# PCLaser.net
KiCad netlist of a schematic drawn in Altium Designer
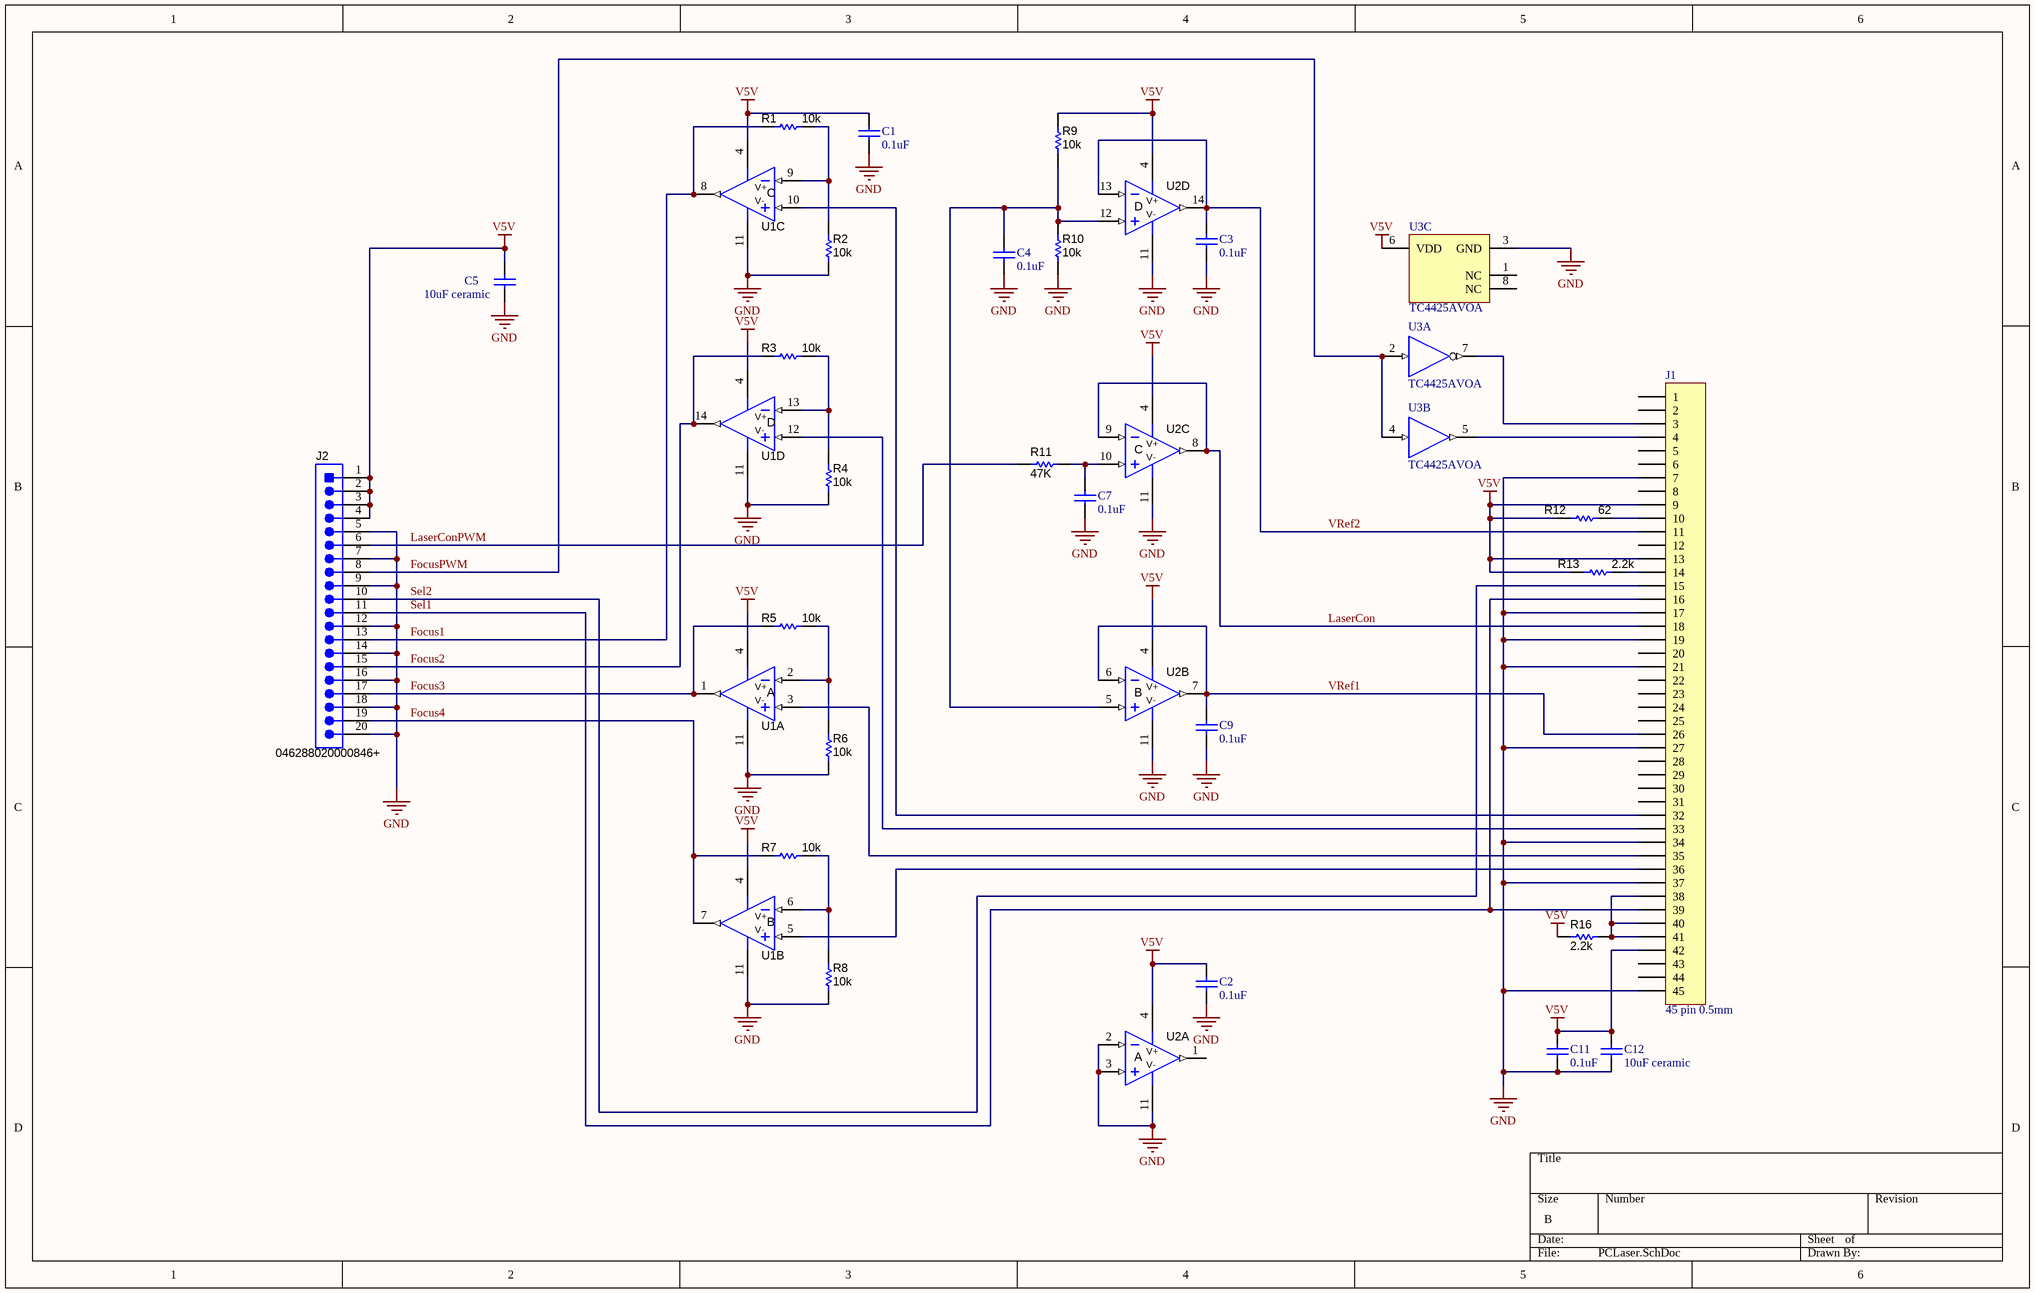
[diagram p0: PCLaser.SchDoc]

(export (version "E")
  (design (tool "Eeschema 10.0.6"))
  (components
    (comp (ref "C1")
      (value "0.1uF")
      (footprint "0603c")
      (description "Capacitor")
      (fields (field (name "PUBLISHER") "Altium Limited"))
      (libsource (lib "Miscellaneous Devices") (part "Cap"))
    )
    (comp (ref "C2")
      (value "0.1uF")
      (footprint "0603c")
      (description "Capacitor")
      (fields (field (name "PUBLISHER") "Altium Limited"))
      (libsource (lib "Miscellaneous Devices") (part "Cap"))
    )
    (comp (ref "C3")
      (value "0.1uF")
      (footprint "0603c")
      (description "Capacitor")
      (fields (field (name "PUBLISHER") "Altium Limited"))
      (libsource (lib "Miscellaneous Devices") (part "Cap"))
    )
    (comp (ref "C4")
      (value "0.1uF")
      (footprint "0603c")
      (description "Capacitor")
      (fields (field (name "PUBLISHER") "Altium Limited"))
      (libsource (lib "Miscellaneous Devices") (part "Cap"))
    )
    (comp (ref "C5")
      (value "10uF ceramic")
      (description "Capacitor")
      (libsource (lib "Miscellaneous Devices") (part "Cap"))
    )
    (comp (ref "C7")
      (value "0.1uF")
      (footprint "0603c")
      (description "Capacitor")
      (fields (field (name "PUBLISHER") "Altium Limited"))
      (libsource (lib "Miscellaneous Devices") (part "Cap"))
    )
    (comp (ref "C9")
      (value "0.1uF")
      (footprint "0603c")
      (description "Capacitor")
      (fields (field (name "PUBLISHER") "Altium Limited"))
      (libsource (lib "Miscellaneous Devices") (part "Cap"))
    )
    (comp (ref "C11")
      (value "0.1uF")
      (footprint "0603c")
      (description "Capacitor")
      (fields (field (name "PUBLISHER") "Altium Limited"))
      (libsource (lib "Miscellaneous Devices") (part "Cap"))
    )
    (comp (ref "C12")
      (value "10uF ceramic")
      (description "Capacitor")
      (libsource (lib "Miscellaneous Devices") (part "Cap"))
    )
    (comp (ref "J1")
      (value "45 pin 0.5mm")
      (footprint "FPC-45x0.5mm")
      (description "Connector")
      (libsource (lib "Steve") (part "CON45"))
    )
    (comp (ref "J2")
      (value "046288020000846+")
      (footprint "FPC20-0.5mm")
      (description "Connector, 20 Pos. 0.5mm R/A SMT Bottom Contact One-Touch Lock, SMT")
      (fields
        (field (name "MANUFACTURER") "Kyocera")
        (field (name "SYMBOLCREATOR") "a0412235")
        (field (name "PUBLISHER") "Texas Instruments")
      )
      (libsource (lib "Connectors_Other") (part "046288020000846+"))
    )
    (comp (ref "R1")
      (value "CRCW060310K0JNEA")
      (footprint "0603")
      (description "RES, 10 k, 5%, 0.1 W, 0603")
      (fields
        (field (name "VALUEDISPLAYED") "10k")
        (field (name "MANUFACTURER") "Vishay-Dale")
        (field (name "PUBLISHER") "Texas Instruments")
      )
      (libsource (lib "Resistor_0603") (part "CRCW060310K0JNEA"))
    )
    (comp (ref "R2")
      (value "CRCW060310K0JNEA")
      (footprint "0603")
      (description "RES, 10 k, 5%, 0.1 W, 0603")
      (fields
        (field (name "VALUEDISPLAYED") "10k")
        (field (name "MANUFACTURER") "Vishay-Dale")
        (field (name "PUBLISHER") "Texas Instruments")
      )
      (libsource (lib "Resistor_0603") (part "CRCW060310K0JNEA"))
    )
    (comp (ref "R3")
      (value "CRCW060310K0JNEA")
      (footprint "0603")
      (description "RES, 10 k, 5%, 0.1 W, 0603")
      (fields
        (field (name "VALUEDISPLAYED") "10k")
        (field (name "MANUFACTURER") "Vishay-Dale")
        (field (name "PUBLISHER") "Texas Instruments")
      )
      (libsource (lib "Resistor_0603") (part "CRCW060310K0JNEA"))
    )
    (comp (ref "R4")
      (value "CRCW060310K0JNEA")
      (footprint "0603")
      (description "RES, 10 k, 5%, 0.1 W, 0603")
      (fields
        (field (name "VALUEDISPLAYED") "10k")
        (field (name "MANUFACTURER") "Vishay-Dale")
        (field (name "PUBLISHER") "Texas Instruments")
      )
      (libsource (lib "Resistor_0603") (part "CRCW060310K0JNEA"))
    )
    (comp (ref "R5")
      (value "CRCW060310K0JNEA")
      (footprint "0603")
      (description "RES, 10 k, 5%, 0.1 W, 0603")
      (fields
        (field (name "VALUEDISPLAYED") "10k")
        (field (name "MANUFACTURER") "Vishay-Dale")
        (field (name "PUBLISHER") "Texas Instruments")
      )
      (libsource (lib "Resistor_0603") (part "CRCW060310K0JNEA"))
    )
    (comp (ref "R6")
      (value "CRCW060310K0JNEA")
      (footprint "0603")
      (description "RES, 10 k, 5%, 0.1 W, 0603")
      (fields
        (field (name "VALUEDISPLAYED") "10k")
        (field (name "MANUFACTURER") "Vishay-Dale")
        (field (name "PUBLISHER") "Texas Instruments")
      )
      (libsource (lib "Resistor_0603") (part "CRCW060310K0JNEA"))
    )
    (comp (ref "R7")
      (value "CRCW060310K0JNEA")
      (footprint "0603")
      (description "RES, 10 k, 5%, 0.1 W, 0603")
      (fields
        (field (name "VALUEDISPLAYED") "10k")
        (field (name "MANUFACTURER") "Vishay-Dale")
        (field (name "PUBLISHER") "Texas Instruments")
      )
      (libsource (lib "Resistor_0603") (part "CRCW060310K0JNEA"))
    )
    (comp (ref "R8")
      (value "CRCW060310K0JNEA")
      (footprint "0603")
      (description "RES, 10 k, 5%, 0.1 W, 0603")
      (fields
        (field (name "VALUEDISPLAYED") "10k")
        (field (name "MANUFACTURER") "Vishay-Dale")
        (field (name "PUBLISHER") "Texas Instruments")
      )
      (libsource (lib "Resistor_0603") (part "CRCW060310K0JNEA"))
    )
    (comp (ref "R9")
      (value "CRCW060310K0JNEA")
      (footprint "0603")
      (description "RES, 10 k, 5%, 0.1 W, 0603")
      (fields
        (field (name "VALUEDISPLAYED") "10k")
        (field (name "MANUFACTURER") "Vishay-Dale")
        (field (name "PUBLISHER") "Texas Instruments")
      )
      (libsource (lib "Resistor_0603") (part "CRCW060310K0JNEA"))
    )
    (comp (ref "R10")
      (value "CRCW060310K0JNEA")
      (footprint "0603")
      (description "RES, 10 k, 5%, 0.1 W, 0603")
      (fields
        (field (name "VALUEDISPLAYED") "10k")
        (field (name "MANUFACTURER") "Vishay-Dale")
        (field (name "PUBLISHER") "Texas Instruments")
      )
      (libsource (lib "Resistor_0603") (part "CRCW060310K0JNEA"))
    )
    (comp (ref "R11")
      (value "~")
      (footprint "0603")
      (description "RES, 47K, 1%, 0.1 W, 0603")
      (fields
        (field (name "VALUEDISPLAYED") "47K")
        (field (name "MANUFACTURER") "Vishay-Dale")
        (field (name "PUBLISHER") "Texas Instruments")
      )
      (libsource (lib "Resistor_0603") (part "CRCW060310K0JNEA"))
    )
    (comp (ref "R12")
      (value "CRCW060362R0JNEA")
      (footprint "0603")
      (description "RES, 62, 5%, 0.1 W, 0603")
      (fields
        (field (name "VALUEDISPLAYED") "62")
        (field (name "MANUFACTURER") "Vishay-Dale")
        (field (name "PUBLISHER") "Texas Instruments")
      )
      (libsource (lib "Resistor_0603") (part "CRCW060362R0JNEA"))
    )
    (comp (ref "R13")
      (value "CRCW06032K20JNEA")
      (footprint "0603")
      (description "RES, 2.2 k, 5%, 0.1 W, 0603")
      (fields
        (field (name "VALUEDISPLAYED") "2.2k")
        (field (name "MANUFACTURER") "Vishay-Dale")
        (field (name "PUBLISHER") "Texas Instruments")
      )
      (libsource (lib "Resistor_0603") (part "CRCW06032K20JNEA"))
    )
    (comp (ref "R16")
      (value "CRCW06032K20JNEA")
      (footprint "0603")
      (description "RES, 2.2 k, 5%, 0.1 W, 0603")
      (fields
        (field (name "VALUEDISPLAYED") "2.2k")
        (field (name "MANUFACTURER") "Vishay-Dale")
        (field (name "PUBLISHER") "Texas Instruments")
      )
      (libsource (lib "Resistor_0603") (part "CRCW06032K20JNEA"))
    )
    (comp (ref "U1")
      (value "LM324KPW")
      (footprint "PW0014A_N")
      (description "Quad Low Power Op Amp with 2KV ESD protection, PW0014A")
      (fields
        (field (name "MANUFACTURER") "Texas Instruments")
        (field (name "SYMBOLCREATOR") "a0412235")
        (field (name "PUBLISHER") "Texas Instruments")
      )
      (libsource (lib "NSC Amplifier") (part "LM324KPW"))
    )
    (comp (ref "U2")
      (value "LM324KPW")
      (footprint "PW0014A_N")
      (description "Quad Low Power Op Amp with 2KV ESD protection, PW0014A")
      (fields
        (field (name "MANUFACTURER") "Texas Instruments")
        (field (name "SYMBOLCREATOR") "a0412235")
        (field (name "PUBLISHER") "Texas Instruments")
      )
      (libsource (lib "NSC Amplifier") (part "LM324KPW"))
    )
    (comp (ref "U3")
      (value "TC4425AVOA")
      (footprint "SOIC-OA8_N")
      (description "3A Dual High-Speed Power MOSFET Drivers, Complimentary, Extended Temperature")
      (fields (field (name "PUBLISHER") "Altium Limited"))
      (libsource (lib "Microchip Power Mgt MOSFET Driver") (part "TC4425AVOA"))
    )
  )
  (nets
    (net (code "1") (name "/Focus1") (class "Default")
      (node (ref "J2") (pin "13") (pinfunction "13_13") (pintype "passive"))
      (node (ref "R1") (pin "2") (pinfunction "2_2") (pintype "passive"))
      (node (ref "U1") (pin "8") (pinfunction "OUT_8") (pintype "output"))
    )
    (net (code "2") (name "/Focus2") (class "Default")
      (node (ref "J2") (pin "15") (pinfunction "15_15") (pintype "passive"))
      (node (ref "R3") (pin "2") (pinfunction "2_2") (pintype "passive"))
      (node (ref "U1") (pin "14") (pinfunction "OUT_14") (pintype "output"))
    )
    (net (code "3") (name "/Focus3") (class "Default")
      (node (ref "J2") (pin "17") (pinfunction "17_17") (pintype "passive"))
      (node (ref "R5") (pin "2") (pinfunction "2_2") (pintype "passive"))
      (node (ref "U1") (pin "1") (pinfunction "OUT_1") (pintype "output"))
    )
    (net (code "4") (name "/Focus4") (class "Default")
      (node (ref "J2") (pin "19") (pinfunction "19_19") (pintype "passive"))
      (node (ref "R7") (pin "2") (pinfunction "2_2") (pintype "passive"))
      (node (ref "U1") (pin "7") (pinfunction "OUT_7") (pintype "output"))
    )
    (net (code "5") (name "/FocusPWM") (class "Default")
      (node (ref "J2") (pin "8") (pinfunction "8_8") (pintype "passive"))
      (node (ref "U3") (pin "2") (pinfunction "INA_2") (pintype "input"))
      (node (ref "U3") (pin "4") (pinfunction "INB_4") (pintype "input"))
    )
    (net (code "6") (name "/LaserCon") (class "Default")
      (node (ref "J1") (pin "18") (pinfunction "18_18") (pintype "passive"))
      (node (ref "U2") (pin "8") (pinfunction "OUT_8") (pintype "output"))
      (node (ref "U2") (pin "9") (pinfunction "IN-_9") (pintype "input"))
    )
    (net (code "7") (name "/LaserConPWM") (class "Default")
      (node (ref "J2") (pin "6") (pinfunction "6_6") (pintype "passive"))
      (node (ref "R11") (pin "2") (pinfunction "2_2") (pintype "passive"))
    )
    (net (code "8") (name "/Sel1") (class "Default")
      (node (ref "J1") (pin "16") (pinfunction "16_16") (pintype "passive"))
      (node (ref "J1") (pin "39") (pinfunction "39_39") (pintype "passive"))
      (node (ref "J2") (pin "11") (pinfunction "11_11") (pintype "passive"))
    )
    (net (code "9") (name "/Sel2") (class "Default")
      (node (ref "J1") (pin "15") (pinfunction "15_15") (pintype "passive"))
      (node (ref "J2") (pin "10") (pinfunction "10_10") (pintype "passive"))
    )
    (net (code "10") (name "/VRef1") (class "Default")
      (node (ref "C9") (pin "2") (pinfunction "2_2") (pintype "passive"))
      (node (ref "J1") (pin "26") (pinfunction "26_26") (pintype "passive"))
      (node (ref "U2") (pin "6") (pinfunction "IN-_6") (pintype "input"))
      (node (ref "U2") (pin "7") (pinfunction "OUT_7") (pintype "output"))
    )
    (net (code "11") (name "/VRef2") (class "Default")
      (node (ref "C3") (pin "2") (pinfunction "2_2") (pintype "passive"))
      (node (ref "J1") (pin "11") (pinfunction "11_11") (pintype "passive"))
      (node (ref "U2") (pin "13") (pinfunction "IN-_13") (pintype "input"))
      (node (ref "U2") (pin "14") (pinfunction "OUT_14") (pintype "output"))
    )
    (net (code "12") (name "GND") (class "Default")
      (node (ref "C1") (pin "1") (pinfunction "1_1") (pintype "passive"))
      (node (ref "C11") (pin "1") (pinfunction "1_1") (pintype "passive"))
      (node (ref "C12") (pin "1") (pinfunction "1_1") (pintype "passive"))
      (node (ref "C2") (pin "1") (pinfunction "1_1") (pintype "passive"))
      (node (ref "C3") (pin "1") (pinfunction "1_1") (pintype "passive"))
      (node (ref "C4") (pin "1") (pinfunction "1_1") (pintype "passive"))
      (node (ref "C5") (pin "1") (pinfunction "1_1") (pintype "passive"))
      (node (ref "C7") (pin "1") (pinfunction "1_1") (pintype "passive"))
      (node (ref "C9") (pin "1") (pinfunction "1_1") (pintype "passive"))
      (node (ref "J1") (pin "17") (pinfunction "17_17") (pintype "passive"))
      (node (ref "J1") (pin "19") (pinfunction "19_19") (pintype "passive"))
      (node (ref "J1") (pin "21") (pinfunction "21_21") (pintype "passive"))
      (node (ref "J1") (pin "27") (pinfunction "27_27") (pintype "passive"))
      (node (ref "J1") (pin "34") (pinfunction "34_34") (pintype "passive"))
      (node (ref "J1") (pin "37") (pinfunction "37_37") (pintype "passive"))
      (node (ref "J1") (pin "45") (pinfunction "45_45") (pintype "passive"))
      (node (ref "J1") (pin "7") (pinfunction "7_7") (pintype "passive"))
      (node (ref "J2") (pin "12") (pinfunction "12_12") (pintype "passive"))
      (node (ref "J2") (pin "14") (pinfunction "14_14") (pintype "passive"))
      (node (ref "J2") (pin "16") (pinfunction "16_16") (pintype "passive"))
      (node (ref "J2") (pin "18") (pinfunction "18_18") (pintype "passive"))
      (node (ref "J2") (pin "20") (pinfunction "20_20") (pintype "passive"))
      (node (ref "J2") (pin "5") (pinfunction "5_5") (pintype "passive"))
      (node (ref "J2") (pin "7") (pinfunction "7_7") (pintype "passive"))
      (node (ref "J2") (pin "9") (pinfunction "9_9") (pintype "passive"))
      (node (ref "R10") (pin "1") (pinfunction "1_1") (pintype "passive"))
      (node (ref "R2") (pin "1") (pinfunction "1_1") (pintype "passive"))
      (node (ref "R4") (pin "1") (pinfunction "1_1") (pintype "passive"))
      (node (ref "R6") (pin "1") (pinfunction "1_1") (pintype "passive"))
      (node (ref "R8") (pin "1") (pinfunction "1_1") (pintype "passive"))
      (node (ref "U1") (pin "11") (pinfunction "V-_11") (pintype "power_in"))
      (node (ref "U2") (pin "11") (pinfunction "V-_11") (pintype "power_in"))
      (node (ref "U2") (pin "2") (pinfunction "IN-_2") (pintype "input"))
      (node (ref "U2") (pin "3") (pinfunction "IN+_3") (pintype "input"))
      (node (ref "U3") (pin "3") (pinfunction "GND_3") (pintype "power_in"))
    )
    (net (code "13") (name "Net-(J1-Pad10)") (class "Default")
      (node (ref "J1") (pin "10") (pinfunction "10_10") (pintype "passive"))
      (node (ref "R12") (pin "1") (pinfunction "1_1") (pintype "passive"))
    )
    (net (code "14") (name "Net-(J1-Pad14)") (class "Default")
      (node (ref "J1") (pin "14") (pinfunction "14_14") (pintype "passive"))
      (node (ref "R13") (pin "1") (pinfunction "1_1") (pintype "passive"))
    )
    (net (code "15") (name "Net-(J1-Pad38)") (class "Default")
      (node (ref "J1") (pin "38") (pinfunction "38_38") (pintype "passive"))
      (node (ref "J1") (pin "40") (pinfunction "40_40") (pintype "passive"))
      (node (ref "J1") (pin "41") (pinfunction "41_41") (pintype "passive"))
      (node (ref "R16") (pin "1") (pinfunction "1_1") (pintype "passive"))
    )
    (net (code "16") (name "Net-(U1A-IN+)") (class "Default")
      (node (ref "J1") (pin "35") (pinfunction "35_35") (pintype "passive"))
      (node (ref "U1") (pin "3") (pinfunction "IN+_3") (pintype "input"))
    )
    (net (code "17") (name "Net-(U1A-IN-)") (class "Default")
      (node (ref "R5") (pin "1") (pinfunction "1_1") (pintype "passive"))
      (node (ref "R6") (pin "2") (pinfunction "2_2") (pintype "passive"))
      (node (ref "U1") (pin "2") (pinfunction "IN-_2") (pintype "input"))
    )
    (net (code "18") (name "Net-(U1B-IN+)") (class "Default")
      (node (ref "J1") (pin "36") (pinfunction "36_36") (pintype "passive"))
      (node (ref "U1") (pin "5") (pinfunction "IN+_5") (pintype "input"))
    )
    (net (code "19") (name "Net-(U1B-IN-)") (class "Default")
      (node (ref "R7") (pin "1") (pinfunction "1_1") (pintype "passive"))
      (node (ref "R8") (pin "2") (pinfunction "2_2") (pintype "passive"))
      (node (ref "U1") (pin "6") (pinfunction "IN-_6") (pintype "input"))
    )
    (net (code "20") (name "Net-(U1C-IN+)") (class "Default")
      (node (ref "J1") (pin "32") (pinfunction "32_32") (pintype "passive"))
      (node (ref "U1") (pin "10") (pinfunction "IN+_10") (pintype "input"))
    )
    (net (code "21") (name "Net-(U1C-IN-)") (class "Default")
      (node (ref "R1") (pin "1") (pinfunction "1_1") (pintype "passive"))
      (node (ref "R2") (pin "2") (pinfunction "2_2") (pintype "passive"))
      (node (ref "U1") (pin "9") (pinfunction "IN-_9") (pintype "input"))
    )
    (net (code "22") (name "Net-(U1D-IN+)") (class "Default")
      (node (ref "J1") (pin "33") (pinfunction "33_33") (pintype "passive"))
      (node (ref "U1") (pin "12") (pinfunction "IN+_12") (pintype "input"))
    )
    (net (code "23") (name "Net-(U1D-IN-)") (class "Default")
      (node (ref "R3") (pin "1") (pinfunction "1_1") (pintype "passive"))
      (node (ref "R4") (pin "2") (pinfunction "2_2") (pintype "passive"))
      (node (ref "U1") (pin "13") (pinfunction "IN-_13") (pintype "input"))
    )
    (net (code "24") (name "Net-(U2B-IN+)") (class "Default")
      (node (ref "C4") (pin "2") (pinfunction "2_2") (pintype "passive"))
      (node (ref "R10") (pin "2") (pinfunction "2_2") (pintype "passive"))
      (node (ref "R9") (pin "1") (pinfunction "1_1") (pintype "passive"))
      (node (ref "U2") (pin "12") (pinfunction "IN+_12") (pintype "input"))
      (node (ref "U2") (pin "5") (pinfunction "IN+_5") (pintype "input"))
    )
    (net (code "25") (name "Net-(U2C-IN+)") (class "Default")
      (node (ref "C7") (pin "2") (pinfunction "2_2") (pintype "passive"))
      (node (ref "R11") (pin "1") (pinfunction "1_1") (pintype "passive"))
      (node (ref "U2") (pin "10") (pinfunction "IN+_10") (pintype "input"))
    )
    (net (code "26") (name "Net-(U3A-~{OUTA})") (class "Default")
      (node (ref "J1") (pin "3") (pinfunction "3_3") (pintype "passive"))
      (node (ref "U3") (pin "7") (pinfunction "~{OUTA}_7") (pintype "output"))
    )
    (net (code "27") (name "Net-(U3B-OUTB)") (class "Default")
      (node (ref "J1") (pin "4") (pinfunction "4_4") (pintype "passive"))
      (node (ref "U3") (pin "5") (pinfunction "OUTB_5") (pintype "output"))
    )
    (net (code "28") (name "V5V") (class "Default")
      (node (ref "C1") (pin "2") (pinfunction "2_2") (pintype "passive"))
      (node (ref "C11") (pin "2") (pinfunction "2_2") (pintype "passive"))
      (node (ref "C12") (pin "2") (pinfunction "2_2") (pintype "passive"))
      (node (ref "C2") (pin "2") (pinfunction "2_2") (pintype "passive"))
      (node (ref "C5") (pin "2") (pinfunction "2_2") (pintype "passive"))
      (node (ref "J1") (pin "13") (pinfunction "13_13") (pintype "passive"))
      (node (ref "J1") (pin "42") (pinfunction "42_42") (pintype "passive"))
      (node (ref "J1") (pin "9") (pinfunction "9_9") (pintype "passive"))
      (node (ref "J2") (pin "1") (pinfunction "1_1") (pintype "passive"))
      (node (ref "J2") (pin "2") (pinfunction "2_2") (pintype "passive"))
      (node (ref "J2") (pin "3") (pinfunction "3_3") (pintype "passive"))
      (node (ref "J2") (pin "4") (pinfunction "4_4") (pintype "passive"))
      (node (ref "R12") (pin "2") (pinfunction "2_2") (pintype "passive"))
      (node (ref "R13") (pin "2") (pinfunction "2_2") (pintype "passive"))
      (node (ref "R16") (pin "2") (pinfunction "2_2") (pintype "passive"))
      (node (ref "R9") (pin "2") (pinfunction "2_2") (pintype "passive"))
      (node (ref "U1") (pin "4") (pinfunction "V+_4") (pintype "power_in"))
      (node (ref "U2") (pin "4") (pinfunction "V+_4") (pintype "power_in"))
      (node (ref "U3") (pin "6") (pinfunction "VDD_6") (pintype "power_in"))
    )
    (net (code "29") (name "unconnected-(J1-Pad1)") (class "Default")
      (node (ref "J1") (pin "1") (pinfunction "1_1") (pintype "passive"))
    )
    (net (code "30") (name "unconnected-(J1-Pad2)") (class "Default")
      (node (ref "J1") (pin "2") (pinfunction "2_2") (pintype "passive"))
    )
    (net (code "31") (name "unconnected-(J1-Pad5)") (class "Default")
      (node (ref "J1") (pin "5") (pinfunction "5_5") (pintype "passive"))
    )
    (net (code "32") (name "unconnected-(J1-Pad6)") (class "Default")
      (node (ref "J1") (pin "6") (pinfunction "6_6") (pintype "passive"))
    )
    (net (code "33") (name "unconnected-(J1-Pad8)") (class "Default")
      (node (ref "J1") (pin "8") (pinfunction "8_8") (pintype "passive"))
    )
    (net (code "34") (name "unconnected-(J1-Pad12)") (class "Default")
      (node (ref "J1") (pin "12") (pinfunction "12_12") (pintype "passive"))
    )
    (net (code "35") (name "unconnected-(J1-Pad20)") (class "Default")
      (node (ref "J1") (pin "20") (pinfunction "20_20") (pintype "passive"))
    )
    (net (code "36") (name "unconnected-(J1-Pad22)") (class "Default")
      (node (ref "J1") (pin "22") (pinfunction "22_22") (pintype "passive"))
    )
    (net (code "37") (name "unconnected-(J1-Pad23)") (class "Default")
      (node (ref "J1") (pin "23") (pinfunction "23_23") (pintype "passive"))
    )
    (net (code "38") (name "unconnected-(J1-Pad24)") (class "Default")
      (node (ref "J1") (pin "24") (pinfunction "24_24") (pintype "passive"))
    )
    (net (code "39") (name "unconnected-(J1-Pad25)") (class "Default")
      (node (ref "J1") (pin "25") (pinfunction "25_25") (pintype "passive"))
    )
    (net (code "40") (name "unconnected-(J1-Pad28)") (class "Default")
      (node (ref "J1") (pin "28") (pinfunction "28_28") (pintype "passive"))
    )
    (net (code "41") (name "unconnected-(J1-Pad29)") (class "Default")
      (node (ref "J1") (pin "29") (pinfunction "29_29") (pintype "passive"))
    )
    (net (code "42") (name "unconnected-(J1-Pad30)") (class "Default")
      (node (ref "J1") (pin "30") (pinfunction "30_30") (pintype "passive"))
    )
    (net (code "43") (name "unconnected-(J1-Pad31)") (class "Default")
      (node (ref "J1") (pin "31") (pinfunction "31_31") (pintype "passive"))
    )
    (net (code "44") (name "unconnected-(J1-Pad43)") (class "Default")
      (node (ref "J1") (pin "43") (pinfunction "43_43") (pintype "passive"))
    )
    (net (code "45") (name "unconnected-(J1-Pad44)") (class "Default")
      (node (ref "J1") (pin "44") (pinfunction "44_44") (pintype "passive"))
    )
    (net (code "46") (name "unconnected-(U2A-OUT-Pad1)") (class "Default")
      (node (ref "U2") (pin "1") (pinfunction "OUT_1") (pintype "output"))
    )
    (net (code "47") (name "unconnected-(U3C-NC-Pad1)") (class "Default")
      (node (ref "U3") (pin "1") (pinfunction "NC_1") (pintype "passive"))
    )
    (net (code "48") (name "unconnected-(U3C-NC-Pad8)") (class "Default")
      (node (ref "U3") (pin "8") (pinfunction "NC_8") (pintype "passive"))
    )
  )
)
